# Driver.net
KiCad netlist of a schematic drawn in Altium Designer
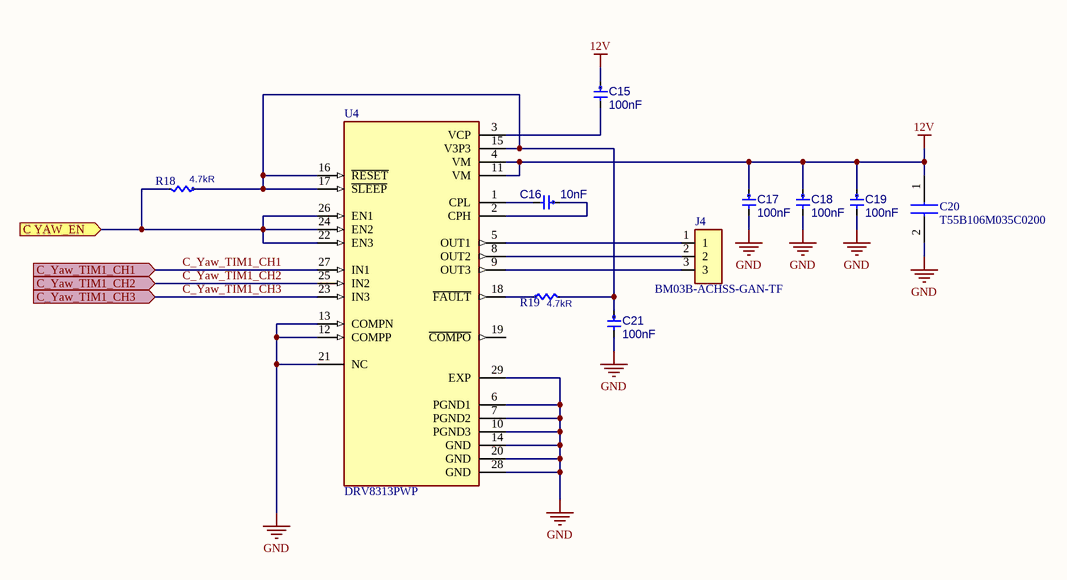
[diagram p0: Driver.SchDoc]

(export (version "E")
  (design (tool "Eeschema 10.0.6"))
  (components
    (comp (ref "C15")
      (value "C0603C104M5RACTU")
      (footprint "CAP0603")
      (description "CAP CER 0.1UF 50V X7R 0603")
      (fields (field (name "TOLERANCE") "20%") (field (name "CAPACITANCE") "100nF"))
      (libsource (lib "rtr") (part "CMP-00691-1"))
    )
    (comp (ref "C16")
      (value "C0603C103M5RACTU")
      (footprint "CAP0603")
      (description "CAP CER 10NF 50V X7R 0603")
      (fields (field (name "TOLERANCE") "20%") (field (name "CAPACITANCE") "10nF"))
      (libsource (lib "rtr") (part "CMP-00691-1"))
    )
    (comp (ref "C17")
      (value "C0603C104M5RACTU")
      (footprint "CAP0603")
      (description "CAP CER 0.1UF 50V X7R 0603")
      (fields (field (name "TOLERANCE") "20%") (field (name "CAPACITANCE") "100nF"))
      (libsource (lib "rtr") (part "CMP-00691-1"))
    )
    (comp (ref "C18")
      (value "C0603C104M5RACTU")
      (footprint "CAP0603")
      (description "CAP CER 0.1UF 50V X7R 0603")
      (fields (field (name "TOLERANCE") "20%") (field (name "CAPACITANCE") "100nF"))
      (libsource (lib "rtr") (part "CMP-00691-1"))
    )
    (comp (ref "C19")
      (value "C0603C104M5RACTU")
      (footprint "CAP0603")
      (description "CAP CER 0.1UF 50V X7R 0603")
      (fields (field (name "TOLERANCE") "20%") (field (name "CAPACITANCE") "100nF"))
      (libsource (lib "rtr") (part "CMP-00691-1"))
    )
    (comp (ref "C20")
      (value "T55B106M035C0200")
      (footprint "T55B106M035C0200")
      (description "Capacitor")
      (fields (field (name "MOUSER PART NUMBER") "74-T55B106M035C0200"))
      (libsource (lib "T55B106M035C0200") (part "T55B106M035C0200"))
    )
    (comp (ref "C21")
      (value "C0603C104M5RACTU")
      (footprint "CAP0603")
      (description "CAP CER 0.1UF 50V X7R 0603")
      (fields (field (name "TOLERANCE") "20%") (field (name "CAPACITANCE") "100nF"))
      (libsource (lib "rtr") (part "CMP-00691-1"))
    )
    (comp (ref "J4")
      (value "BM03B-ACHSS-GAN-TF")
      (footprint "BM03B-ACHSS-GAN-TF")
      (description "ACH Series 3 Position 1.2 mm Pitch Disconnectable Crimp Style Housing")
      (libsource (lib "SM02B-SFKH-TF") (part "BM03B-ACHSS-GAN-TF"))
    )
    (comp (ref "R18")
      (value "RC0603JR-074K7L")
      (footprint "RES0603")
      (description "RES SMD 4.7K OHM 5% 1/10W 0603")
      (fields (field (name "TOLERANCE") "5%") (field (name "RESISTANCE") "4.7kR"))
      (libsource (lib "rtr") (part "CMP-01404-1"))
    )
    (comp (ref "R19")
      (value "RC0603JR-074K7L")
      (footprint "RES0603")
      (description "RES SMD 4.7K OHM 5% 1/10W 0603")
      (fields (field (name "TOLERANCE") "5%") (field (name "RESISTANCE") "4.7kR"))
      (libsource (lib "rtr") (part "CMP-01404-1"))
    )
    (comp (ref "U4")
      (value "DRV8313PWP")
      (footprint "DRV8313PWP")
      (description "65-V max, 3-A peak 3-phase motor driver")
      (fields (field (name "MF") "Texas Instruments"))
      (libsource (lib "STM32H743VIT6") (part "DRV8313PWP"))
    )
  )
  (nets
    (net (code "1") (name "/C YAW_EN") (class "Default")
      (node (ref "R18") (pin "2") (pinfunction "2_2") (pintype "passive"))
      (node (ref "U4") (pin "22") (pinfunction "EN3_22") (pintype "input"))
      (node (ref "U4") (pin "24") (pinfunction "EN2_24") (pintype "input"))
      (node (ref "U4") (pin "26") (pinfunction "EN1_26") (pintype "input"))
    )
    (net (code "2") (name "/C_Yaw_TIM1_CH1") (class "Default")
      (node (ref "U4") (pin "27") (pinfunction "IN1_27") (pintype "input"))
    )
    (net (code "3") (name "/C_Yaw_TIM1_CH2") (class "Default")
      (node (ref "U4") (pin "25") (pinfunction "IN2_25") (pintype "input"))
    )
    (net (code "4") (name "/C_Yaw_TIM1_CH3") (class "Default")
      (node (ref "U4") (pin "23") (pinfunction "IN3_23") (pintype "input"))
    )
    (net (code "5") (name "12V") (class "Default")
      (node (ref "C15") (pin "1") (pinfunction "1_1") (pintype "passive"))
      (node (ref "C17") (pin "1") (pinfunction "1_1") (pintype "passive"))
      (node (ref "C18") (pin "1") (pinfunction "1_1") (pintype "passive"))
      (node (ref "C19") (pin "1") (pinfunction "1_1") (pintype "passive"))
      (node (ref "C20") (pin "1") (pinfunction "1_1") (pintype "passive"))
      (node (ref "U4") (pin "11") (pinfunction "VM_11") (pintype "power_in"))
      (node (ref "U4") (pin "4") (pinfunction "VM_4") (pintype "power_in"))
    )
    (net (code "6") (name "GND") (class "Default")
      (node (ref "C17") (pin "2") (pinfunction "2_2") (pintype "passive"))
      (node (ref "C18") (pin "2") (pinfunction "2_2") (pintype "passive"))
      (node (ref "C19") (pin "2") (pinfunction "2_2") (pintype "passive"))
      (node (ref "C20") (pin "2") (pinfunction "2_2") (pintype "passive"))
      (node (ref "C21") (pin "2") (pinfunction "2_2") (pintype "passive"))
      (node (ref "U4") (pin "10") (pinfunction "PGND3_10") (pintype "power_in"))
      (node (ref "U4") (pin "12") (pinfunction "COMPP_12") (pintype "input"))
      (node (ref "U4") (pin "13") (pinfunction "COMPN_13") (pintype "input"))
      (node (ref "U4") (pin "14") (pinfunction "GND_14") (pintype "power_in"))
      (node (ref "U4") (pin "20") (pinfunction "GND_20") (pintype "power_in"))
      (node (ref "U4") (pin "21") (pinfunction "NC_21") (pintype "passive"))
      (node (ref "U4") (pin "28") (pinfunction "GND_28") (pintype "power_in"))
      (node (ref "U4") (pin "29") (pinfunction "EXP_29") (pintype "power_in"))
      (node (ref "U4") (pin "6") (pinfunction "PGND1_6") (pintype "power_in"))
      (node (ref "U4") (pin "7") (pinfunction "PGND2_7") (pintype "power_in"))
    )
    (net (code "7") (name "Net-(U4-CPH)") (class "Default")
      (node (ref "C16") (pin "1") (pinfunction "1_1") (pintype "passive"))
      (node (ref "U4") (pin "2") (pinfunction "CPH_2") (pintype "power_in"))
    )
    (net (code "8") (name "Net-(U4-CPL)") (class "Default")
      (node (ref "C16") (pin "2") (pinfunction "2_2") (pintype "passive"))
      (node (ref "U4") (pin "1") (pinfunction "CPL_1") (pintype "power_in"))
    )
    (net (code "9") (name "Net-(U4-OUT1)") (class "Default")
      (node (ref "J4") (pin "1") (pinfunction "1_1") (pintype "passive"))
      (node (ref "U4") (pin "5") (pinfunction "OUT1_5") (pintype "output"))
    )
    (net (code "10") (name "Net-(U4-OUT2)") (class "Default")
      (node (ref "J4") (pin "2") (pinfunction "2_2") (pintype "passive"))
      (node (ref "U4") (pin "8") (pinfunction "OUT2_8") (pintype "output"))
    )
    (net (code "11") (name "Net-(U4-OUT3)") (class "Default")
      (node (ref "J4") (pin "3") (pinfunction "3_3") (pintype "passive"))
      (node (ref "U4") (pin "9") (pinfunction "OUT3_9") (pintype "output"))
    )
    (net (code "12") (name "Net-(U4-V3P3)") (class "Default")
      (node (ref "C21") (pin "1") (pinfunction "1_1") (pintype "passive"))
      (node (ref "R18") (pin "1") (pinfunction "1_1") (pintype "passive"))
      (node (ref "R19") (pin "2") (pinfunction "2_2") (pintype "passive"))
      (node (ref "U4") (pin "15") (pinfunction "V3P3_15") (pintype "power_in"))
      (node (ref "U4") (pin "16") (pinfunction "~{RESET}_16") (pintype "input"))
      (node (ref "U4") (pin "17") (pinfunction "~{SLEEP}_17") (pintype "input"))
    )
    (net (code "13") (name "Net-(U4-VCP)") (class "Default")
      (node (ref "C15") (pin "2") (pinfunction "2_2") (pintype "passive"))
      (node (ref "U4") (pin "3") (pinfunction "VCP_3") (pintype "power_in"))
    )
    (net (code "14") (name "Net-(U4-~{FAULT})") (class "Default")
      (node (ref "R19") (pin "1") (pinfunction "1_1") (pintype "passive"))
      (node (ref "U4") (pin "18") (pinfunction "~{FAULT}_18") (pintype "output"))
    )
    (net (code "15") (name "unconnected-(U4-~{COMPO}-Pad19)") (class "Default")
      (node (ref "U4") (pin "19") (pinfunction "~{COMPO}_19") (pintype "output"))
    )
  )
)
